# Base_Module.net
KiCad netlist of a schematic drawn in Altium Designer
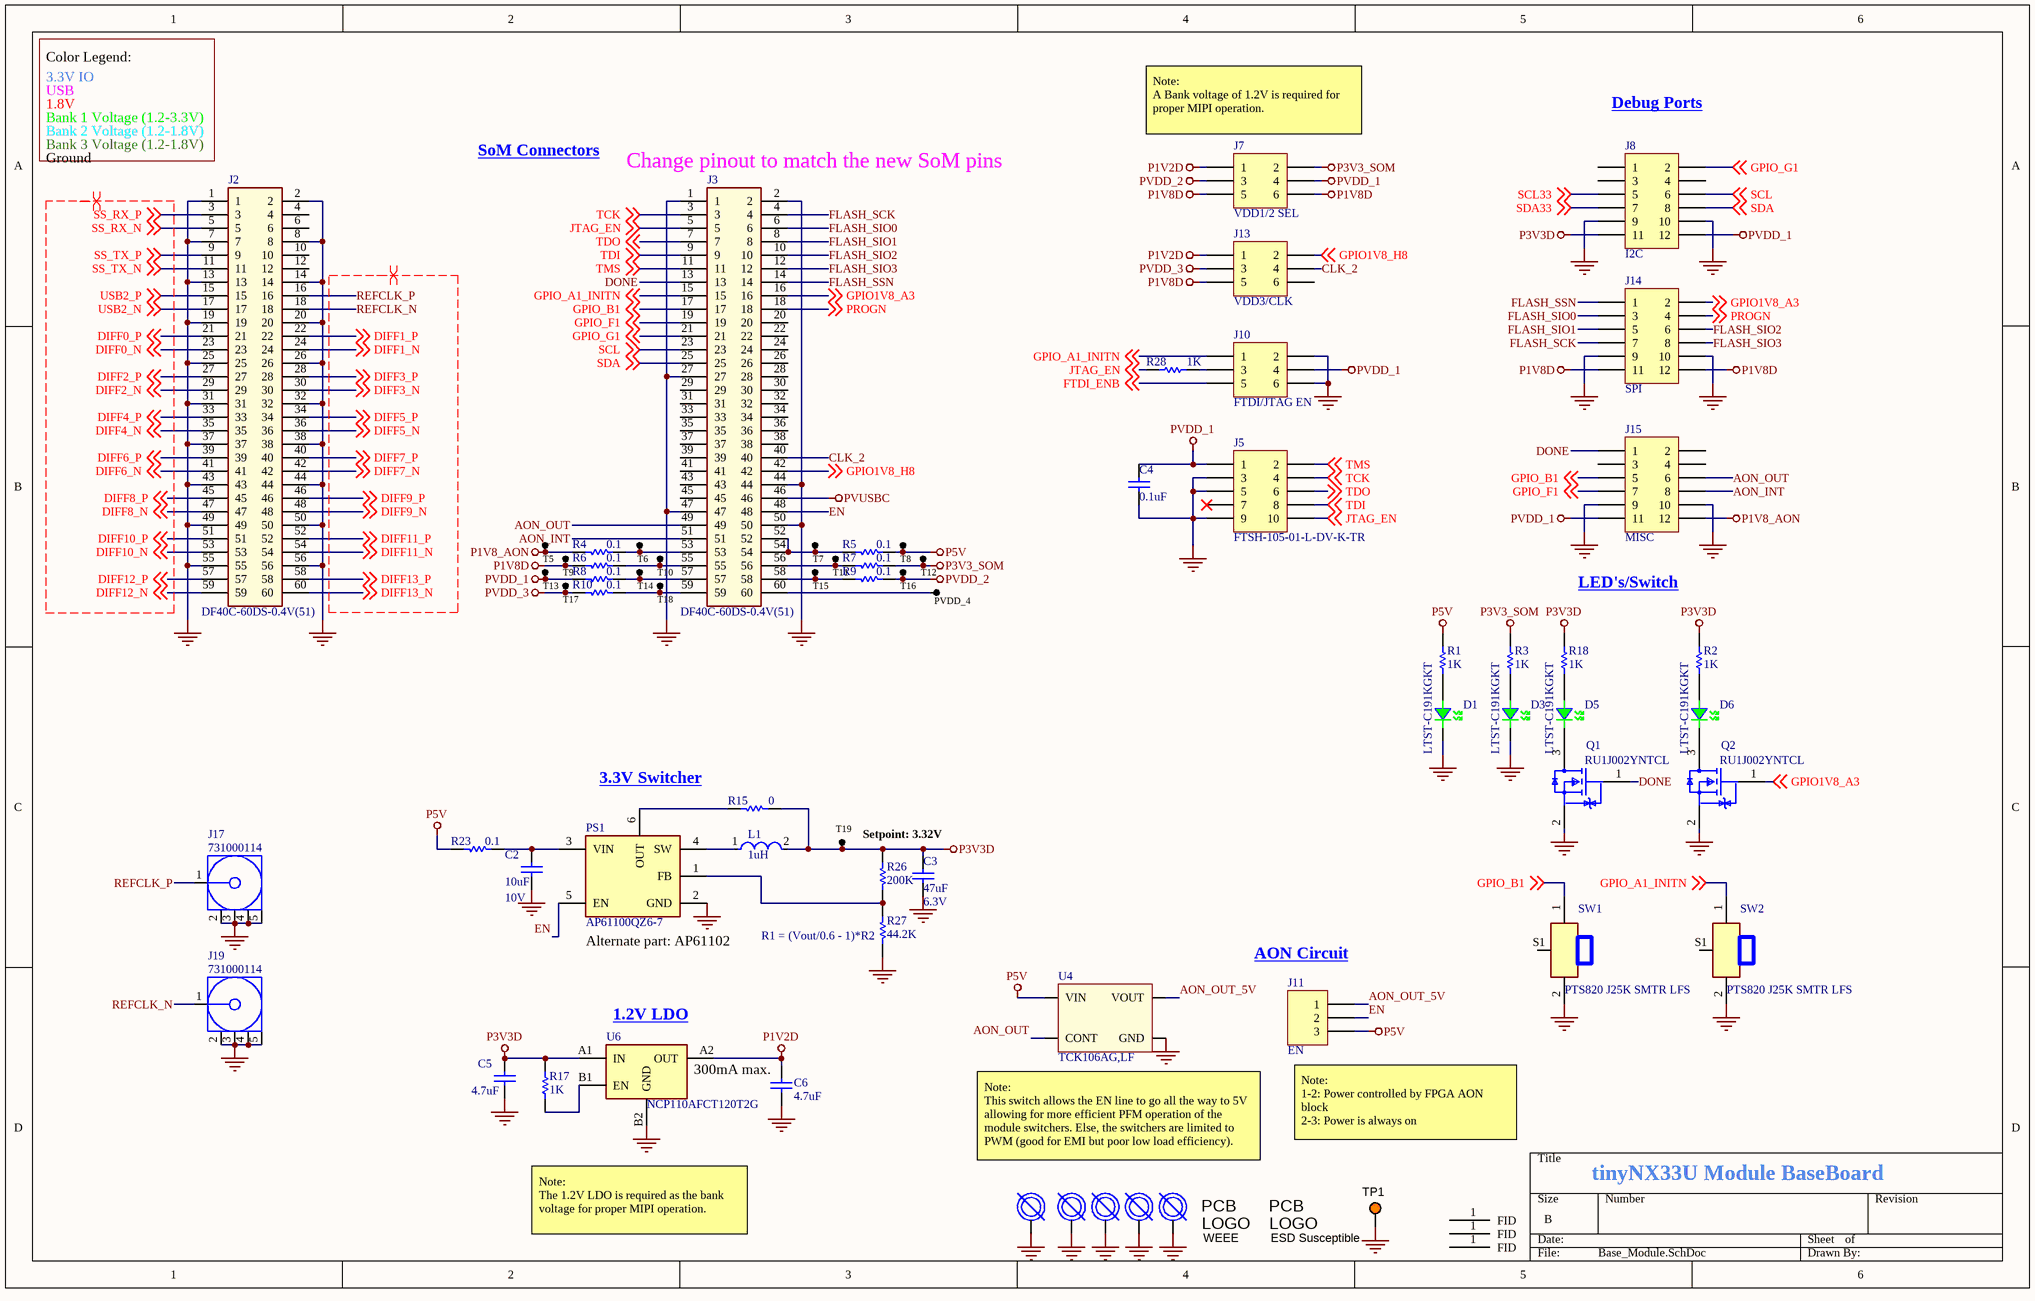
[diagram p0: Base_Module.SchDoc]

(export (version "E")
  (design (tool "Eeschema 10.0.6"))
  (components
    (comp (ref "BH1")
      (value "STANDOFF M2.5")
      (footprint "MH_3MM")
      (description "ROUND STANDOFF M2X0.4 STEEL 1MM")
      (libsource (lib "MIPI_xlator") (part "MOUNT_HOLE"))
    )
    (comp (ref "BH2")
      (value "STANDOFF M2.5")
      (footprint "MH_3MM")
      (description "ROUND STANDOFF M2X0.4 STEEL 1MM")
      (libsource (lib "MIPI_xlator") (part "MOUNT_HOLE"))
    )
    (comp (ref "BH3")
      (value "STANDOFF M2.5")
      (footprint "MH_3MM")
      (description "ROUND STANDOFF M2X0.4 STEEL 1MM")
      (libsource (lib "MIPI_xlator") (part "MOUNT_HOLE"))
    )
    (comp (ref "BH4")
      (value "STANDOFF M2.5")
      (footprint "MH_3MM")
      (description "ROUND STANDOFF M2X0.4 STEEL 1MM")
      (libsource (lib "MIPI_xlator") (part "MOUNT_HOLE"))
    )
    (comp (ref "BH5")
      (value "STANDOFF M2.5")
      (footprint "MH_3MM")
      (description "ROUND STANDOFF M2X0.4 STEEL 1MM")
      (libsource (lib "MIPI_xlator") (part "MOUNT_HOLE"))
    )
    (comp (ref "C2")
      (value "10uF")
      (footprint "CAP_0603")
      (description "CAP CER 10uF 10V X5R 0603")
      (fields
        (field (name "MANUFACTURER PART NUMBER") "GRM188R61A106ME69D")
        (field (name "MANUFACTURER") "Murata Electronics")
        (field (name "VOLTAGE") "10V")
      )
      (libsource (lib "Smart Camera") (part "Cap_1uF_X5R_10%_6V3_0402"))
    )
    (comp (ref "C3")
      (value "47uF")
      (footprint "CAP_0603")
      (description "CAP CER 47UF 6.3V X5R 0603")
      (fields
        (field (name "MANUFACTURER PART NUMBER") "GRM188R60J476ME15D")
        (field (name "MANUFACTURER") "Murata Electronics")
        (field (name "VOLTAGE") "6.3V")
      )
      (libsource (lib "Smart Camera") (part "Cap_1uF_X5R_10%_6V3_0402"))
    )
    (comp (ref "C4")
      (value "0.1uF")
      (footprint "CAPC1005X55USR")
      (description "CAP CER 0.1UF 16V X7R 0402")
      (fields
        (field (name "MANUFACTURER PART NUMBER") "CGA2B1X7R1C104K050BC")
        (field (name "MANUFACTURER") "TDK Corporation")
      )
      (libsource (lib "NX Module baseboard") (part "CAP CER 0.1UF 16V X7R 0402"))
    )
    (comp (ref "C5")
      (value "4.7uF")
      (footprint "CAPC1005X55USR")
      (description "CAP CER 4.7UF 10V X5R 0402")
      (fields
        (field (name "MANUFACTURER PART NUMBER") "C1005X5R1A475M050BC")
        (field (name "MANUFACTURER") "TDK Corporation")
      )
      (libsource (lib "NX Module baseboard") (part "CAP CER 4.7UF 10V X5R 0402"))
    )
    (comp (ref "C6")
      (value "4.7uF")
      (footprint "CAPC1005X55USR")
      (description "CAP CER 4.7UF 10V X5R 0402")
      (fields
        (field (name "MANUFACTURER PART NUMBER") "C1005X5R1A475M050BC")
        (field (name "MANUFACTURER") "TDK Corporation")
      )
      (libsource (lib "NX Module baseboard") (part "CAP CER 4.7UF 10V X5R 0402"))
    )
    (comp (ref "D1")
      (value "LTST-C191KGKT")
      (footprint "LED_0603")
      (description "LED GREEN CLEAR CHIP 0603 SMD")
      (fields
        (field (name "MANUFACTURER") "Lite-On Inc.")
        (field (name "MANUFACTURER PART NUMBER") "LTST-C191GKT")
      )
      (libsource (lib "Tiger_Ti180") (part "0603LED_GRN"))
    )
    (comp (ref "D3")
      (value "LTST-C191KGKT")
      (footprint "LED_0603")
      (description "LED GREEN CLEAR CHIP 0603 SMD")
      (fields
        (field (name "MANUFACTURER") "Lite-On Inc.")
        (field (name "MANUFACTURER PART NUMBER") "LTST-C191GKT")
      )
      (libsource (lib "Tiger_Ti180") (part "0603LED_GRN"))
    )
    (comp (ref "D5")
      (value "LTST-C191KGKT")
      (footprint "LED_0603")
      (description "LED GREEN CLEAR CHIP 0603 SMD")
      (fields
        (field (name "MANUFACTURER") "Lite-On Inc.")
        (field (name "MANUFACTURER PART NUMBER") "LTST-C191GKT")
      )
      (libsource (lib "Tiger_Ti180") (part "0603LED_GRN"))
    )
    (comp (ref "D6")
      (value "LTST-C191KGKT")
      (footprint "LED_0603")
      (description "LED GREEN CLEAR CHIP 0603 SMD")
      (fields
        (field (name "MANUFACTURER") "Lite-On Inc.")
        (field (name "MANUFACTURER PART NUMBER") "LTST-C191GKT")
      )
      (libsource (lib "Tiger_Ti180") (part "0603LED_GRN"))
    )
    (comp (ref "FID1") (value "~") (footprint "FID_040") (libsource (lib "MIPI_xlator") (part "FID")))
    (comp (ref "FID2") (value "~") (footprint "FID_040") (libsource (lib "MIPI_xlator") (part "FID")))
    (comp (ref "FID3") (value "~") (footprint "FID_040") (libsource (lib "MIPI_xlator") (part "FID")))
    (comp (ref "J2")
      (value "DF40C-60DS-0.4V(51)")
      (footprint "DF40C60DS04V51")
      (description "CONN RCPT 60POS SMD GOLD")
      (fields (field (name "MANUFACTURER") "Hirose"))
      (libsource (lib "NX Module baseboard") (part "DF40C-60DS-0.4V(51)"))
    )
    (comp (ref "J3")
      (value "DF40C-60DS-0.4V(51)")
      (footprint "DF40C60DS04V51")
      (description "CONN RCPT 60POS SMD GOLD")
      (fields (field (name "MANUFACTURER") "Hirose"))
      (libsource (lib "NX Module baseboard") (part "DF40C-60DS-0.4V(51)"))
    )
    (comp (ref "J5")
      (value "FTSH-105-01-L-DV-K-TR")
      (footprint "FTSH-105-01-XXX-DV-K")
      (description "CONN HEADER SMD 10POS 1.27MM")
      (fields (field (name "MANUFACTURER") "Samtec Inc."))
      (libsource (lib "tinyAI") (part "HDR2X5_1.27mm"))
    )
    (comp (ref "J7")
      (value "Header 3X2_SMD")
      (footprint "HDR3X2_MALE_2.54MM_SAMTEC-A-TSM-103")
      (description "Conn Unshrouded Header HDR 6 POS 2.54mm Solder ST Top Entry SMD Tube")
      (fields
        (field (name "MANUFACTURER") "Samtec")
        (field (name "MANUFACTURER PART NUMBER") "TSM-103-01-L-DV")
        (field (name "CONTENT") "VDD1/2 SEL")
      )
      (libsource (lib "NX Module baseboard") (part "Header 3X2_SMD"))
    )
    (comp (ref "J8")
      (value "Header 6X2_SMD")
      (footprint "HDR6X2_MALE_2.54MM_SAMTEC-A-TSM-106")
      (description "Conn Unshrouded Header HDR 12 POS 2.54mm Solder ST Top Entry SMD Tube")
      (fields
        (field (name "MANUFACTURER") "Samtec")
        (field (name "MANUFACTURER PART NUMBER") "TSM-106-01-L-DV")
        (field (name "CONTENT") "I2C")
      )
      (libsource (lib "NX Module baseboard") (part "Header 6X2_SMD"))
    )
    (comp (ref "J10")
      (value "Header 3X2_SMD")
      (footprint "HDR3X2_MALE_2.54MM_SAMTEC-A-TSM-103")
      (description "Conn Unshrouded Header HDR 6 POS 2.54mm Solder ST Top Entry SMD Tube")
      (fields
        (field (name "MANUFACTURER") "Samtec")
        (field (name "MANUFACTURER PART NUMBER") "TSM-103-01-L-DV")
        (field (name "CONTENT") "FTDI/JTAG EN")
      )
      (libsource (lib "NX Module baseboard") (part "Header 3X2_SMD"))
    )
    (comp (ref "J11")
      (value "Header 3X1_2.54MM")
      (footprint "HDR3X1_MALE_2.54MM")
      (description "CONN HEADER .100 SNGL STR 3POS")
      (fields
        (field (name "MANUFACTURER") "Sullins")
        (field (name "MANUFACTURER PART NUMBER") "PRPC003SAAN-RC")
        (field (name "CONTENT") "EN")
      )
      (libsource (lib "NX Module baseboard") (part "Header 3X1_2.54MM"))
    )
    (comp (ref "J13")
      (value "Header 3X2_SMD")
      (footprint "HDR3X2_MALE_2.54MM_SAMTEC-A-TSM-103")
      (description "Conn Unshrouded Header HDR 6 POS 2.54mm Solder ST Top Entry SMD Tube")
      (fields
        (field (name "MANUFACTURER") "Samtec")
        (field (name "MANUFACTURER PART NUMBER") "TSM-103-01-L-DV")
        (field (name "CONTENT") "VDD3/CLK")
      )
      (libsource (lib "NX Module baseboard") (part "Header 3X2_SMD"))
    )
    (comp (ref "J14")
      (value "Header 6X2_SMD")
      (footprint "HDR6X2_MALE_2.54MM_SAMTEC-A-TSM-106")
      (description "Conn Unshrouded Header HDR 12 POS 2.54mm Solder ST Top Entry SMD Tube")
      (fields
        (field (name "MANUFACTURER") "Samtec")
        (field (name "MANUFACTURER PART NUMBER") "TSM-106-01-L-DV")
        (field (name "CONTENT") "SPI")
      )
      (libsource (lib "NX Module baseboard") (part "Header 6X2_SMD"))
    )
    (comp (ref "J15")
      (value "Header 6X2_SMD")
      (footprint "HDR6X2_MALE_2.54MM_SAMTEC-A-TSM-106")
      (description "Conn Unshrouded Header HDR 12 POS 2.54mm Solder ST Top Entry SMD Tube")
      (fields
        (field (name "MANUFACTURER") "Samtec")
        (field (name "MANUFACTURER PART NUMBER") "TSM-106-01-L-DV")
        (field (name "CONTENT") "MISC")
      )
      (libsource (lib "NX Module baseboard") (part "Header 6X2_SMD"))
    )
    (comp (ref "J17")
      (value "731000114")
      (footprint "0731000114")
      (description "SMA Right-Angle PCB Jack Receptacle, Brass Body, Gold Plated, 50 Ohm, 5-Pin THD, RoHS, Tray")
      (fields (field (name "MANUFACTURER") "Molex") (field (name "MANUFACTURER PART NUMBER") "73100-0114"))
      (libsource (lib "NX Module baseboard") (part "CN-S-4F-RF5"))
    )
    (comp (ref "J19")
      (value "731000114")
      (footprint "0731000114")
      (description "SMA Right-Angle PCB Jack Receptacle, Brass Body, Gold Plated, 50 Ohm, 5-Pin THD, RoHS, Tray")
      (fields (field (name "MANUFACTURER") "Molex") (field (name "MANUFACTURER PART NUMBER") "73100-0114"))
      (libsource (lib "NX Module baseboard") (part "CN-S-4F-RF5"))
    )
    (comp (ref "L1")
      (value "1uH")
      (footprint "INDC2016X100N")
      (description "FIXED IND 1UH 2.7A 57 MOHM SMD")
      (fields
        (field (name "MANUFACTURER") "Murata Electronics")
        (field (name "MANUFACTURER PART NUMBER") "DFE201610E-1R0M=P2")
      )
      (libsource (lib "Smart Camera") (part "725321dda6339637d4d059423bc1c3c"))
    )
    (comp (ref "Logo1")
      (value "WEEE")
      (footprint "WEEE_Minimum")
      (description "WEEE logo")
      (libsource (lib "MIPI_xlator") (part "Logo WEEE"))
    )
    (comp (ref "Logo2")
      (value "ESD Susceptible")
      (footprint "ESD_Overlay_Medium")
      (description "ESD Susceptible Symbol")
      (fields (field (name "PUBLISHER") "Texas Instruments") (field (name "SYMBOLCREATOR") "a0412235"))
      (libsource (lib "MIPI_xlator") (part "Logo ESD"))
    )
    (comp (ref "PS1")
      (value "AP61100QZ6-7")
      (footprint "SOTFL50P160X60-6N")
      (description "DC-DC CONV LV BUCK SOT563")
      (fields (field (name "MANUFACTURER") "Diodes Incorporated"))
      (libsource (lib "Smart Camera") (part "AP61100Z6-7"))
    )
    (comp (ref "PVDD_4")
      (value "TP_S")
      (footprint "TP_TH")
      (description "test point")
      (libsource (lib "AiC") (part "TP_S"))
    )
    (comp (ref "Q1")
      (value "RU1J002YNTCL")
      (footprint "SOT-323FL")
      (description "MOSFET N-CH 50V 0.2A UMT3F")
      (fields
        (field (name "MANUFACTURER") "Rohm")
        (field (name "OCTOPART") "https://octopart.com/ru1j002yntcl-rohm-47197697")
      )
      (libsource (lib "AiC") (part "1926738d861a973c8d722c53ec8fd09"))
    )
    (comp (ref "Q2")
      (value "RU1J002YNTCL")
      (footprint "SOT-323FL")
      (description "MOSFET N-CH 50V 0.2A UMT3F")
      (fields
        (field (name "MANUFACTURER") "Rohm")
        (field (name "OCTOPART") "https://octopart.com/ru1j002yntcl-rohm-47197697")
      )
      (libsource (lib "AiC") (part "1926738d861a973c8d722c53ec8fd09"))
    )
    (comp (ref "R1")
      (value "1K")
      (footprint "RESC1005X40USR")
      (description "RES SMD 1K OHM 1% 1/16W 0402")
      (fields
        (field (name "MANUFACTURER") "YAGEO")
        (field (name "MANUFACTURER PART NUMBER") "RC0402FR-071KL")
      )
      (libsource (lib "Tiger_Ti180") (part "RES 1K OHM 1% 1/16W 0402"))
    )
    (comp (ref "R2")
      (value "1K")
      (footprint "RESC1005X40USR")
      (description "RES SMD 1K OHM 1% 1/16W 0402")
      (fields
        (field (name "MANUFACTURER") "YAGEO")
        (field (name "MANUFACTURER PART NUMBER") "RC0402FR-071KL")
      )
      (libsource (lib "Tiger_Ti180") (part "RES 1K OHM 1% 1/16W 0402"))
    )
    (comp (ref "R3")
      (value "1K")
      (footprint "RESC1005X40USR")
      (description "RES SMD 1K OHM 1% 1/16W 0402")
      (fields
        (field (name "MANUFACTURER") "YAGEO")
        (field (name "MANUFACTURER PART NUMBER") "RC0402FR-071KL")
      )
      (libsource (lib "Tiger_Ti180") (part "RES 1K OHM 1% 1/16W 0402"))
    )
    (comp (ref "R4")
      (value "0.1")
      (footprint "RESC1005X40USR")
      (description "RES 0.1 OHM 1% 1/8W 0402")
      (fields
        (field (name "MANUFACTURER PART NUMBER") "CSR0402FKR100")
        (field (name "MANUFACTURER") "Stackpole Electronics Inc")
      )
      (libsource (lib "tinyAI") (part "RES 0.5 OHM 1% 1/8W 0402"))
    )
    (comp (ref "R5")
      (value "0.1")
      (footprint "RESC1005X40USR")
      (description "RES 0.1 OHM 1% 1/8W 0402")
      (fields
        (field (name "MANUFACTURER PART NUMBER") "CSR0402FKR100")
        (field (name "MANUFACTURER") "Stackpole Electronics Inc")
      )
      (libsource (lib "tinyAI") (part "RES 0.5 OHM 1% 1/8W 0402"))
    )
    (comp (ref "R6")
      (value "0.1")
      (footprint "RESC1005X40USR")
      (description "RES 0.1 OHM 1% 1/8W 0402")
      (fields
        (field (name "MANUFACTURER PART NUMBER") "CSR0402FKR100")
        (field (name "MANUFACTURER") "Stackpole Electronics Inc")
      )
      (libsource (lib "tinyAI") (part "RES 0.5 OHM 1% 1/8W 0402"))
    )
    (comp (ref "R7")
      (value "0.1")
      (footprint "RESC1005X40USR")
      (description "RES 0.1 OHM 1% 1/8W 0402")
      (fields
        (field (name "MANUFACTURER PART NUMBER") "CSR0402FKR100")
        (field (name "MANUFACTURER") "Stackpole Electronics Inc")
      )
      (libsource (lib "tinyAI") (part "RES 0.5 OHM 1% 1/8W 0402"))
    )
    (comp (ref "R8")
      (value "0.1")
      (footprint "RESC1005X40USR")
      (description "RES 0.1 OHM 1% 1/8W 0402")
      (fields
        (field (name "MANUFACTURER PART NUMBER") "CSR0402FKR100")
        (field (name "MANUFACTURER") "Stackpole Electronics Inc")
      )
      (libsource (lib "tinyAI") (part "RES 0.5 OHM 1% 1/8W 0402"))
    )
    (comp (ref "R9")
      (value "0.1")
      (footprint "RESC1005X40USR")
      (description "RES 0.1 OHM 1% 1/8W 0402")
      (fields
        (field (name "MANUFACTURER PART NUMBER") "CSR0402FKR100")
        (field (name "MANUFACTURER") "Stackpole Electronics Inc")
      )
      (libsource (lib "tinyAI") (part "RES 0.5 OHM 1% 1/8W 0402"))
    )
    (comp (ref "R10")
      (value "0.1")
      (footprint "RESC1005X40USR")
      (description "RES 0.1 OHM 1% 1/8W 0402")
      (fields
        (field (name "MANUFACTURER PART NUMBER") "CSR0402FKR100")
        (field (name "MANUFACTURER") "Stackpole Electronics Inc")
      )
      (libsource (lib "tinyAI") (part "RES 0.5 OHM 1% 1/8W 0402"))
    )
    (comp (ref "R15")
      (value "0")
      (footprint "RESC1005X40USR")
      (description "RES 0 OHM JUMPER 1/16W 0402")
      (fields
        (field (name "MANUFACTURER") "Yageo")
        (field (name "MANUFACTURER PART NUMBER") "RC0402JR-070RL")
      )
      (libsource (lib "Smart Camera v2") (part "RES 0 OHM JUMPER 1/20W 0201"))
    )
    (comp (ref "R17")
      (value "1K")
      (footprint "RESC1005X40USR")
      (description "RES SMD 1K OHM 1% 1/16W 0402")
      (fields
        (field (name "MANUFACTURER") "YAGEO")
        (field (name "MANUFACTURER PART NUMBER") "RC0402FR-071KL")
      )
      (libsource (lib "Tiger_Ti180") (part "RES 1K OHM 1% 1/16W 0402"))
    )
    (comp (ref "R18")
      (value "1K")
      (footprint "RESC1005X40USR")
      (description "RES SMD 1K OHM 1% 1/16W 0402")
      (fields
        (field (name "MANUFACTURER") "YAGEO")
        (field (name "MANUFACTURER PART NUMBER") "RC0402FR-071KL")
      )
      (libsource (lib "Tiger_Ti180") (part "RES 1K OHM 1% 1/16W 0402"))
    )
    (comp (ref "R23")
      (value "0.1")
      (footprint "RESC1005X40USR")
      (description "RES 0.1 OHM 1% 1/8W 0402")
      (fields
        (field (name "MANUFACTURER PART NUMBER") "CSR0402FKR100")
        (field (name "MANUFACTURER") "Stackpole Electronics Inc")
      )
      (libsource (lib "tinyAI") (part "RES 0.5 OHM 1% 1/8W 0402"))
    )
    (comp (ref "R26")
      (value "200K")
      (footprint "RESC1005X40USR")
      (description "RES SMD 200K OHM 1% 1/16W 0402")
      (fields
        (field (name "MANUFACTURER") "Stackpole Electronics Inc")
        (field (name "MANUFACTURER PART NUMBER") "RMCF0402FT200K")
      )
      (libsource (lib "MCD_Temp_LBE") (part "Res_10K_1%_0402"))
    )
    (comp (ref "R27")
      (value "44.2K")
      (footprint "RESC1005X40USR")
      (description "RES SMD 44.2K OHM 1% 1/16W 0402")
      (fields
        (field (name "MANUFACTURER") "Yageo")
        (field (name "MANUFACTURER PART NUMBER") "RC0402FR-0744K2L")
      )
      (libsource (lib "MCD_Temp_LBE") (part "Res_10K_1%_0402"))
    )
    (comp (ref "R28")
      (value "1K")
      (footprint "RESC1005X40USR")
      (description "RES SMD 1K OHM 1% 1/16W 0402")
      (fields
        (field (name "MANUFACTURER") "YAGEO")
        (field (name "MANUFACTURER PART NUMBER") "RC0402FR-071KL")
      )
      (libsource (lib "Tiger_Ti180") (part "RES 1K OHM 1% 1/16W 0402"))
    )
    (comp (ref "SW1")
      (value "PTS820 J25K SMTR LFS")
      (footprint "PTS820J25MSMTRLFS")
      (description "SWITCH TACTILE SPST-NO 0.05A 12V")
      (fields (field (name "MANUFACTURER") "C&K"))
      (libsource (lib "Tiger_Ti180") (part "SPST_NO"))
    )
    (comp (ref "SW2")
      (value "PTS820 J25K SMTR LFS")
      (footprint "PTS820J25MSMTRLFS")
      (description "SWITCH TACTILE SPST-NO 0.05A 12V")
      (fields (field (name "MANUFACTURER") "C&K"))
      (libsource (lib "Tiger_Ti180") (part "SPST_NO"))
    )
    (comp (ref "T5")
      (value "TP_S")
      (footprint "TP_TH")
      (description "test point")
      (libsource (lib "AiC") (part "TP_S"))
    )
    (comp (ref "T6")
      (value "TP_S")
      (footprint "TP_TH")
      (description "test point")
      (libsource (lib "AiC") (part "TP_S"))
    )
    (comp (ref "T7")
      (value "TP_S")
      (footprint "TP_TH")
      (description "test point")
      (libsource (lib "AiC") (part "TP_S"))
    )
    (comp (ref "T8")
      (value "TP_S")
      (footprint "TP_TH")
      (description "test point")
      (libsource (lib "AiC") (part "TP_S"))
    )
    (comp (ref "T9")
      (value "TP_S")
      (footprint "TP_TH")
      (description "test point")
      (libsource (lib "AiC") (part "TP_S"))
    )
    (comp (ref "T10")
      (value "TP_S")
      (footprint "TP_TH")
      (description "test point")
      (libsource (lib "AiC") (part "TP_S"))
    )
    (comp (ref "T11")
      (value "TP_S")
      (footprint "TP_TH")
      (description "test point")
      (libsource (lib "AiC") (part "TP_S"))
    )
    (comp (ref "T12")
      (value "TP_S")
      (footprint "TP_TH")
      (description "test point")
      (libsource (lib "AiC") (part "TP_S"))
    )
    (comp (ref "T13")
      (value "TP_S")
      (footprint "TP_TH")
      (description "test point")
      (libsource (lib "AiC") (part "TP_S"))
    )
    (comp (ref "T14")
      (value "TP_S")
      (footprint "TP_TH")
      (description "test point")
      (libsource (lib "AiC") (part "TP_S"))
    )
    (comp (ref "T15")
      (value "TP_S")
      (footprint "TP_TH")
      (description "test point")
      (libsource (lib "AiC") (part "TP_S"))
    )
    (comp (ref "T16")
      (value "TP_S")
      (footprint "TP_TH")
      (description "test point")
      (libsource (lib "AiC") (part "TP_S"))
    )
    (comp (ref "T17")
      (value "TP_S")
      (footprint "TP_TH")
      (description "test point")
      (libsource (lib "AiC") (part "TP_S"))
    )
    (comp (ref "T18")
      (value "TP_S")
      (footprint "TP_TH")
      (description "test point")
      (libsource (lib "AiC") (part "TP_S"))
    )
    (comp (ref "T19")
      (value "3V3")
      (footprint "TP 1mm")
      (description "test point")
      (libsource (lib "Smart Camera") (part "TP_S"))
    )
    (comp (ref "TP1")
      (value "5019")
      (footprint "TP380X203")
      (description "PC TEST POINT MINIATURE")
      (fields (field (name "MANUFACTURER") "Keystone Electronics"))
      (libsource (lib "MIPI_xlator") (part "5019"))
    )
    (comp (ref "U4")
      (value "TCK106AG,LF")
      (footprint "WCSP4D")
      (description "IC PWR SWITCH P-CHAN 1:1 4WCSPD")
      (fields
        (field (name "MANUFACTURER") "Toshiba")
        (field (name "COPYRIGHT") "Copyright (C) 2018 Accelerated Designs. All rights reserved")
      )
      (libsource (lib "tinyAI") (part "TCK106AG"))
    )
    (comp (ref "U6")
      (value "NCP110AFCT120T2G")
      (footprint "WLCSP4_P6XP6_ONS")
      (description "LDO Regulator, 200 mA, Low Vin, Ultra-High PSRR 1.2V, Active Discharge")
      (fields (field (name "MANUFACTURER") "ON Semiconductor"))
      (libsource (lib "Tiger_Ti180") (part "NCP110AFCT120T2G"))
    )
  )
  (nets
    (net (code "1") (name "/AON_INT") (class "Default")
      (node (ref "J15") (pin "8") (pinfunction "8_8") (pintype "passive"))
      (node (ref "J3") (pin "51") (pinfunction "51_51") (pintype "passive"))
    )
    (net (code "2") (name "/AON_OUT") (class "Default")
      (node (ref "J15") (pin "6") (pinfunction "6_6") (pintype "passive"))
      (node (ref "J3") (pin "49") (pinfunction "49_49") (pintype "passive"))
      (node (ref "U4") (pin "B2") (pinfunction "CONT_B2") (pintype "passive"))
    )
    (net (code "3") (name "/AON_OUT_5V") (class "Default")
      (node (ref "J11") (pin "1") (pinfunction "1_1") (pintype "passive"))
      (node (ref "U4") (pin "A1") (pinfunction "VOUT_A1") (pintype "passive"))
    )
    (net (code "4") (name "/CLK_2") (class "Default")
      (node (ref "J13") (pin "4") (pinfunction "4_4") (pintype "passive"))
      (node (ref "J3") (pin "40") (pinfunction "40_40") (pintype "passive"))
    )
    (net (code "5") (name "/DONE") (class "Default")
      (node (ref "J15") (pin "1") (pinfunction "1_1") (pintype "passive"))
      (node (ref "J3") (pin "13") (pinfunction "13_13") (pintype "passive"))
      (node (ref "Q1") (pin "1") (pinfunction "G_1") (pintype "passive"))
    )
    (net (code "6") (name "/EN") (class "Default")
      (node (ref "J11") (pin "2") (pinfunction "2_2") (pintype "passive"))
      (node (ref "J3") (pin "48") (pinfunction "48_48") (pintype "passive"))
      (node (ref "PS1") (pin "5") (pinfunction "EN_5") (pintype "passive"))
    )
    (net (code "7") (name "/FLASH_SCK") (class "Default")
      (node (ref "J14") (pin "7") (pinfunction "7_7") (pintype "passive"))
      (node (ref "J3") (pin "4") (pinfunction "4_4") (pintype "passive"))
    )
    (net (code "8") (name "/FLASH_SIO0") (class "Default")
      (node (ref "J14") (pin "3") (pinfunction "3_3") (pintype "passive"))
      (node (ref "J3") (pin "6") (pinfunction "6_6") (pintype "passive"))
    )
    (net (code "9") (name "/FLASH_SIO1") (class "Default")
      (node (ref "J14") (pin "5") (pinfunction "5_5") (pintype "passive"))
      (node (ref "J3") (pin "8") (pinfunction "8_8") (pintype "passive"))
    )
    (net (code "10") (name "/FLASH_SIO2") (class "Default")
      (node (ref "J14") (pin "6") (pinfunction "6_6") (pintype "passive"))
      (node (ref "J3") (pin "10") (pinfunction "10_10") (pintype "passive"))
    )
    (net (code "11") (name "/FLASH_SIO3") (class "Default")
      (node (ref "J14") (pin "8") (pinfunction "8_8") (pintype "passive"))
      (node (ref "J3") (pin "12") (pinfunction "12_12") (pintype "passive"))
    )
    (net (code "12") (name "/FLASH_SSN") (class "Default")
      (node (ref "J14") (pin "1") (pinfunction "1_1") (pintype "passive"))
      (node (ref "J3") (pin "14") (pinfunction "14_14") (pintype "passive"))
    )
    (net (code "13") (name "/REFCLK_N") (class "Default")
      (node (ref "J19") (pin "1") (pinfunction "1_1") (pintype "passive"))
      (node (ref "J2") (pin "18") (pinfunction "18_18") (pintype "passive"))
    )
    (net (code "14") (name "/REFCLK_P") (class "Default")
      (node (ref "J17") (pin "1") (pinfunction "1_1") (pintype "passive"))
      (node (ref "J2") (pin "16") (pinfunction "16_16") (pintype "passive"))
    )
    (net (code "15") (name "DIFF0_N") (class "Default")
      (node (ref "J2") (pin "23") (pinfunction "23_23") (pintype "passive"))
    )
    (net (code "16") (name "DIFF0_P") (class "Default")
      (node (ref "J2") (pin "21") (pinfunction "21_21") (pintype "passive"))
    )
    (net (code "17") (name "DIFF1_N") (class "Default")
      (node (ref "J2") (pin "24") (pinfunction "24_24") (pintype "passive"))
    )
    (net (code "18") (name "DIFF1_P") (class "Default")
      (node (ref "J2") (pin "22") (pinfunction "22_22") (pintype "passive"))
    )
    (net (code "19") (name "DIFF2_N") (class "Default")
      (node (ref "J2") (pin "29") (pinfunction "29_29") (pintype "passive"))
    )
    (net (code "20") (name "DIFF2_P") (class "Default")
      (node (ref "J2") (pin "27") (pinfunction "27_27") (pintype "passive"))
    )
    (net (code "21") (name "DIFF3_N") (class "Default")
      (node (ref "J2") (pin "30") (pinfunction "30_30") (pintype "passive"))
    )
    (net (code "22") (name "DIFF3_P") (class "Default")
      (node (ref "J2") (pin "28") (pinfunction "28_28") (pintype "passive"))
    )
    (net (code "23") (name "DIFF4_N") (class "Default")
      (node (ref "J2") (pin "35") (pinfunction "35_35") (pintype "passive"))
    )
    (net (code "24") (name "DIFF4_P") (class "Default")
      (node (ref "J2") (pin "33") (pinfunction "33_33") (pintype "passive"))
    )
    (net (code "25") (name "DIFF5_N") (class "Default")
      (node (ref "J2") (pin "36") (pinfunction "36_36") (pintype "passive"))
    )
    (net (code "26") (name "DIFF5_P") (class "Default")
      (node (ref "J2") (pin "34") (pinfunction "34_34") (pintype "passive"))
    )
    (net (code "27") (name "DIFF6_N") (class "Default")
      (node (ref "J2") (pin "41") (pinfunction "41_41") (pintype "passive"))
    )
    (net (code "28") (name "DIFF6_P") (class "Default")
      (node (ref "J2") (pin "39") (pinfunction "39_39") (pintype "passive"))
    )
    (net (code "29") (name "DIFF7_N") (class "Default")
      (node (ref "J2") (pin "42") (pinfunction "42_42") (pintype "passive"))
    )
    (net (code "30") (name "DIFF7_P") (class "Default")
      (node (ref "J2") (pin "40") (pinfunction "40_40") (pintype "passive"))
    )
    (net (code "31") (name "DIFF8_N") (class "Default")
      (node (ref "J2") (pin "47") (pinfunction "47_47") (pintype "passive"))
    )
    (net (code "32") (name "DIFF8_P") (class "Default")
      (node (ref "J2") (pin "45") (pinfunction "45_45") (pintype "passive"))
    )
    (net (code "33") (name "DIFF9_N") (class "Default")
      (node (ref "J2") (pin "48") (pinfunction "48_48") (pintype "passive"))
    )
    (net (code "34") (name "DIFF9_P") (class "Default")
      (node (ref "J2") (pin "46") (pinfunction "46_46") (pintype "passive"))
    )
    (net (code "35") (name "DIFF10_N") (class "Default")
      (node (ref "J2") (pin "53") (pinfunction "53_53") (pintype "passive"))
    )
    (net (code "36") (name "DIFF10_P") (class "Default")
      (node (ref "J2") (pin "51") (pinfunction "51_51") (pintype "passive"))
    )
    (net (code "37") (name "DIFF11_N") (class "Default")
      (node (ref "J2") (pin "54") (pinfunction "54_54") (pintype "passive"))
    )
    (net (code "38") (name "DIFF11_P") (class "Default")
      (node (ref "J2") (pin "52") (pinfunction "52_52") (pintype "passive"))
    )
    (net (code "39") (name "DIFF12_N") (class "Default")
      (node (ref "J2") (pin "59") (pinfunction "59_59") (pintype "passive"))
    )
    (net (code "40") (name "DIFF12_P") (class "Default")
      (node (ref "J2") (pin "57") (pinfunction "57_57") (pintype "passive"))
    )
    (net (code "41") (name "DIFF13_N") (class "Default")
      (node (ref "J2") (pin "60") (pinfunction "60_60") (pintype "passive"))
    )
    (net (code "42") (name "DIFF13_P") (class "Default")
      (node (ref "J2") (pin "58") (pinfunction "58_58") (pintype "passive"))
    )
    (net (code "43") (name "FTDI_ENB") (class "Default")
      (node (ref "J10") (pin "5") (pinfunction "5_5") (pintype "passive"))
    )
    (net (code "44") (name "GND") (class "Default")
      (node (ref "BH1") (pin "1") (pinfunction "1_1") (pintype "passive"))
      (node (ref "BH2") (pin "1") (pinfunction "1_1") (pintype "passive"))
      (node (ref "BH3") (pin "1") (pinfunction "1_1") (pintype "passive"))
      (node (ref "BH4") (pin "1") (pinfunction "1_1") (pintype "passive"))
      (node (ref "BH5") (pin "1") (pinfunction "1_1") (pintype "passive"))
      (node (ref "C2") (pin "1") (pinfunction "1_1") (pintype "passive"))
      (node (ref "C3") (pin "1") (pinfunction "1_1") (pintype "passive"))
      (node (ref "C4") (pin "1") (pinfunction "1_1") (pintype "passive"))
      (node (ref "C5") (pin "1") (pinfunction "1_1") (pintype "passive"))
      (node (ref "C6") (pin "1") (pinfunction "1_1") (pintype "passive"))
      (node (ref "D1") (pin "2") (pinfunction "K_2") (pintype "passive"))
      (node (ref "D3") (pin "2") (pinfunction "K_2") (pintype "passive"))
      (node (ref "J10") (pin "2") (pinfunction "2_2") (pintype "passive"))
      (node (ref "J10") (pin "6") (pinfunction "6_6") (pintype "passive"))
      (node (ref "J14") (pin "10") (pinfunction "10_10") (pintype "passive"))
      (node (ref "J14") (pin "9") (pinfunction "9_9") (pintype "passive"))
      (node (ref "J15") (pin "10") (pinfunction "10_10") (pintype "passive"))
      (node (ref "J15") (pin "9") (pinfunction "9_9") (pintype "passive"))
      (node (ref "J17") (pin "2") (pinfunction "2_2") (pintype "passive"))
      (node (ref "J17") (pin "3") (pinfunction "3_3") (pintype "passive"))
      (node (ref "J17") (pin "4") (pinfunction "4_4") (pintype "passive"))
      (node (ref "J17") (pin "5") (pinfunction "5_5") (pintype "passive"))
      (node (ref "J19") (pin "2") (pinfunction "2_2") (pintype "passive"))
      (node (ref "J19") (pin "3") (pinfunction "3_3") (pintype "passive"))
      (node (ref "J19") (pin "4") (pinfunction "4_4") (pintype "passive"))
      (node (ref "J19") (pin "5") (pinfunction "5_5") (pintype "passive"))
      (node (ref "J2") (pin "1") (pinfunction "1_1") (pintype "passive"))
      (node (ref "J2") (pin "13") (pinfunction "13_13") (pintype "passive"))
      (node (ref "J2") (pin "14") (pinfunction "14_14") (pintype "passive"))
      (node (ref "J2") (pin "19") (pinfunction "19_19") (pintype "passive"))
      (node (ref "J2") (pin "2") (pinfunction "2_2") (pintype "passive"))
      (node (ref "J2") (pin "20") (pinfunction "20_20") (pintype "passive"))
      (node (ref "J2") (pin "25") (pinfunction "25_25") (pintype "passive"))
      (node (ref "J2") (pin "26") (pinfunction "26_26") (pintype "passive"))
      (node (ref "J2") (pin "31") (pinfunction "31_31") (pintype "passive"))
      (node (ref "J2") (pin "32") (pinfunction "32_32") (pintype "passive"))
      (node (ref "J2") (pin "37") (pinfunction "37_37") (pintype "passive"))
      (node (ref "J2") (pin "38") (pinfunction "38_38") (pintype "passive"))
      (node (ref "J2") (pin "43") (pinfunction "43_43") (pintype "passive"))
      (node (ref "J2") (pin "44") (pinfunction "44_44") (pintype "passive"))
      (node (ref "J2") (pin "49") (pinfunction "49_49") (pintype "passive"))
      (node (ref "J2") (pin "50") (pinfunction "50_50") (pintype "passive"))
      (node (ref "J2") (pin "55") (pinfunction "55_55") (pintype "passive"))
      (node (ref "J2") (pin "56") (pinfunction "56_56") (pintype "passive"))
      (node (ref "J2") (pin "7") (pinfunction "7_7") (pintype "passive"))
      (node (ref "J2") (pin "8") (pinfunction "8_8") (pintype "passive"))
      (node (ref "J3") (pin "1") (pinfunction "1_1") (pintype "passive"))
      (node (ref "J3") (pin "2") (pinfunction "2_2") (pintype "passive"))
      (node (ref "J3") (pin "27") (pinfunction "27_27") (pintype "passive"))
      (node (ref "J3") (pin "44") (pinfunction "44_44") (pintype "passive"))
      (node (ref "J3") (pin "47") (pinfunction "47_47") (pintype "passive"))
      (node (ref "J3") (pin "50") (pinfunction "50_50") (pintype "passive"))
      (node (ref "J5") (pin "3") (pinfunction "3_3") (pintype "passive"))
      (node (ref "J5") (pin "5") (pinfunction "5_5") (pintype "passive"))
      (node (ref "J5") (pin "9") (pinfunction "9_9") (pintype "passive"))
      (node (ref "J8") (pin "10") (pinfunction "10_10") (pintype "passive"))
      (node (ref "J8") (pin "9") (pinfunction "9_9") (pintype "passive"))
      (node (ref "PS1") (pin "2") (pinfunction "GND_2") (pintype "passive"))
      (node (ref "Q1") (pin "2") (pinfunction "S_2") (pintype "passive"))
      (node (ref "Q2") (pin "2") (pinfunction "S_2") (pintype "passive"))
      (node (ref "R27") (pin "1") (pinfunction "1_1") (pintype "passive"))
      (node (ref "SW1") (pin "2") (pinfunction "2_2") (pintype "passive"))
      (node (ref "SW2") (pin "2") (pinfunction "2_2") (pintype "passive"))
      (node (ref "TP1") (pin "1") (pinfunction "1_1") (pintype "passive"))
      (node (ref "U4") (pin "B1") (pinfunction "GND_B1") (pintype "passive"))
      (node (ref "U6") (pin "B2") (pinfunction "GND_B2") (pintype "passive"))
    )
    (net (code "45") (name "GPIO1V8_A3") (class "Default")
      (node (ref "J14") (pin "2") (pinfunction "2_2") (pintype "passive"))
      (node (ref "J3") (pin "16") (pinfunction "16_16") (pintype "passive"))
      (node (ref "Q2") (pin "1") (pinfunction "G_1") (pintype "passive"))
    )
    (net (code "46") (name "GPIO1V8_H8") (class "Default")
      (node (ref "J13") (pin "2") (pinfunction "2_2") (pintype "passive"))
      (node (ref "J3") (pin "42") (pinfunction "42_42") (pintype "passive"))
    )
    (net (code "47") (name "GPIO_A1_INITN") (class "Default")
      (node (ref "J10") (pin "1") (pinfunction "1_1") (pintype "passive"))
      (node (ref "J3") (pin "15") (pinfunction "15_15") (pintype "passive"))
      (node (ref "SW2") (pin "1") (pinfunction "1_1") (pintype "passive"))
    )
    (net (code "48") (name "GPIO_B1") (class "Default")
      (node (ref "J15") (pin "5") (pinfunction "5_5") (pintype "passive"))
      (node (ref "J3") (pin "17") (pinfunction "17_17") (pintype "passive"))
      (node (ref "SW1") (pin "1") (pinfunction "1_1") (pintype "passive"))
    )
    (net (code "49") (name "GPIO_F1") (class "Default")
      (node (ref "J15") (pin "7") (pinfunction "7_7") (pintype "passive"))
      (node (ref "J3") (pin "19") (pinfunction "19_19") (pintype "passive"))
    )
    (net (code "50") (name "GPIO_G1") (class "Default")
      (node (ref "J3") (pin "21") (pinfunction "21_21") (pintype "passive"))
      (node (ref "J8") (pin "2") (pinfunction "2_2") (pintype "passive"))
    )
    (net (code "51") (name "JTAG_EN") (class "Default")
      (node (ref "J3") (pin "5") (pinfunction "5_5") (pintype "passive"))
      (node (ref "J5") (pin "10") (pinfunction "10_10") (pintype "passive"))
      (node (ref "R28") (pin "1") (pinfunction "1_1") (pintype "passive"))
    )
    (net (code "52") (name "Net-(D1-A)") (class "Default")
      (node (ref "D1") (pin "1") (pinfunction "A_1") (pintype "passive"))
      (node (ref "R1") (pin "2") (pinfunction "2_2") (pintype "passive"))
    )
    (net (code "53") (name "Net-(D3-A)") (class "Default")
      (node (ref "D3") (pin "1") (pinfunction "A_1") (pintype "passive"))
      (node (ref "R3") (pin "2") (pinfunction "2_2") (pintype "passive"))
    )
    (net (code "54") (name "Net-(D5-A)") (class "Default")
      (node (ref "D5") (pin "1") (pinfunction "A_1") (pintype "passive"))
      (node (ref "R18") (pin "2") (pinfunction "2_2") (pintype "passive"))
    )
    (net (code "55") (name "Net-(D5-K)") (class "Default")
      (node (ref "D5") (pin "2") (pinfunction "K_2") (pintype "passive"))
      (node (ref "Q1") (pin "3") (pinfunction "D_3") (pintype "passive"))
    )
    (net (code "56") (name "Net-(D6-A)") (class "Default")
      (node (ref "D6") (pin "1") (pinfunction "A_1") (pintype "passive"))
      (node (ref "R2") (pin "2") (pinfunction "2_2") (pintype "passive"))
    )
    (net (code "57") (name "Net-(D6-K)") (class "Default")
      (node (ref "D6") (pin "2") (pinfunction "K_2") (pintype "passive"))
      (node (ref "Q2") (pin "3") (pinfunction "D_3") (pintype "passive"))
    )
    (net (code "58") (name "Net-(J3-Pad52)") (class "Default")
      (node (ref "J3") (pin "52") (pinfunction "52_52") (pintype "passive"))
      (node (ref "J3") (pin "54") (pinfunction "54_54") (pintype "passive"))
      (node (ref "R5") (pin "2") (pinfunction "2_2") (pintype "passive"))
      (node (ref "T7") (pin "1") (pintype "passive"))
    )
    (net (code "59") (name "Net-(J3-Pad53)") (class "Default")
      (node (ref "J3") (pin "53") (pinfunction "53_53") (pintype "passive"))
      (node (ref "R4") (pin "1") (pinfunction "1_1") (pintype "passive"))
      (node (ref "T6") (pin "1") (pintype "passive"))
    )
    (net (code "60") (name "Net-(J3-Pad55)") (class "Default")
      (node (ref "J3") (pin "55") (pinfunction "55_55") (pintype "passive"))
      (node (ref "R6") (pin "1") (pinfunction "1_1") (pintype "passive"))
      (node (ref "T10") (pin "1") (pintype "passive"))
    )
    (net (code "61") (name "Net-(J3-Pad56)") (class "Default")
      (node (ref "J3") (pin "56") (pinfunction "56_56") (pintype "passive"))
      (node (ref "R7") (pin "2") (pinfunction "2_2") (pintype "passive"))
      (node (ref "T11") (pin "1") (pintype "passive"))
    )
    (net (code "62") (name "Net-(J3-Pad57)") (class "Default")
      (node (ref "J3") (pin "57") (pinfunction "57_57") (pintype "passive"))
      (node (ref "R8") (pin "1") (pinfunction "1_1") (pintype "passive"))
      (node (ref "T14") (pin "1") (pintype "passive"))
    )
    (net (code "63") (name "Net-(J3-Pad58)") (class "Default")
      (node (ref "J3") (pin "58") (pinfunction "58_58") (pintype "passive"))
      (node (ref "R9") (pin "2") (pinfunction "2_2") (pintype "passive"))
      (node (ref "T15") (pin "1") (pintype "passive"))
    )
    (net (code "64") (name "Net-(J3-Pad59)") (class "Default")
      (node (ref "J3") (pin "59") (pinfunction "59_59") (pintype "passive"))
      (node (ref "R10") (pin "1") (pinfunction "1_1") (pintype "passive"))
      (node (ref "T18") (pin "1") (pintype "passive"))
    )
    (net (code "65") (name "Net-(J3-Pad60)") (class "Default")
      (node (ref "J3") (pin "60") (pinfunction "60_60") (pintype "passive"))
      (node (ref "PVDD_4") (pin "1") (pintype "passive"))
    )
    (net (code "66") (name "Net-(J10-Pad3)") (class "Default")
      (node (ref "J10") (pin "3") (pinfunction "3_3") (pintype "passive"))
      (node (ref "R28") (pin "2") (pinfunction "2_2") (pintype "passive"))
    )
    (net (code "67") (name "Net-(PS1-FB)") (class "Default")
      (node (ref "PS1") (pin "1") (pinfunction "FB_1") (pintype "passive"))
      (node (ref "R26") (pin "1") (pinfunction "1_1") (pintype "passive"))
      (node (ref "R27") (pin "2") (pinfunction "2_2") (pintype "passive"))
    )
    (net (code "68") (name "Net-(PS1-OUT)") (class "Default")
      (node (ref "PS1") (pin "6") (pinfunction "OUT_6") (pintype "passive"))
      (node (ref "R15") (pin "2") (pinfunction "2_2") (pintype "passive"))
    )
    (net (code "69") (name "Net-(PS1-SW)") (class "Default")
      (node (ref "L1") (pin "1") (pinfunction "1_1") (pintype "passive"))
      (node (ref "PS1") (pin "4") (pinfunction "SW_4") (pintype "passive"))
    )
    (net (code "70") (name "Net-(PS1-VIN)") (class "Default")
      (node (ref "C2") (pin "2") (pinfunction "2_2") (pintype "passive"))
      (node (ref "PS1") (pin "3") (pinfunction "VIN_3") (pintype "passive"))
      (node (ref "R23") (pin "1") (pinfunction "1_1") (pintype "passive"))
    )
    (net (code "71") (name "Net-(U6-EN)") (class "Default")
      (node (ref "R17") (pin "2") (pinfunction "2_2") (pintype "passive"))
      (node (ref "U6") (pin "B1") (pinfunction "EN_B1") (pintype "passive"))
    )
    (net (code "72") (name "P1V2D") (class "Default")
      (node (ref "C6") (pin "2") (pinfunction "2_2") (pintype "passive"))
      (node (ref "J13") (pin "1") (pinfunction "1_1") (pintype "passive"))
      (node (ref "J7") (pin "1") (pinfunction "1_1") (pintype "passive"))
      (node (ref "U6") (pin "A2") (pinfunction "OUT_A2") (pintype "passive"))
    )
    (net (code "73") (name "P1V8D") (class "Default")
      (node (ref "J13") (pin "5") (pinfunction "5_5") (pintype "passive"))
      (node (ref "J14") (pin "11") (pinfunction "11_11") (pintype "passive"))
      (node (ref "J14") (pin "12") (pinfunction "12_12") (pintype "passive"))
      (node (ref "J7") (pin "5") (pinfunction "5_5") (pintype "passive"))
      (node (ref "J7") (pin "6") (pinfunction "6_6") (pintype "passive"))
      (node (ref "R6") (pin "2") (pinfunction "2_2") (pintype "passive"))
      (node (ref "T9") (pin "1") (pintype "passive"))
    )
    (net (code "74") (name "P1V8_AON") (class "Default")
      (node (ref "J15") (pin "12") (pinfunction "12_12") (pintype "passive"))
      (node (ref "R4") (pin "2") (pinfunction "2_2") (pintype "passive"))
      (node (ref "T5") (pin "1") (pintype "passive"))
    )
    (net (code "75") (name "P3V3D") (class "Default")
      (node (ref "C3") (pin "2") (pinfunction "2_2") (pintype "passive"))
      (node (ref "C5") (pin "2") (pinfunction "2_2") (pintype "passive"))
      (node (ref "J8") (pin "11") (pinfunction "11_11") (pintype "passive"))
      (node (ref "L1") (pin "2") (pinfunction "2_2") (pintype "passive"))
      (node (ref "R15") (pin "1") (pinfunction "1_1") (pintype "passive"))
      (node (ref "R17") (pin "1") (pinfunction "1_1") (pintype "passive"))
      (node (ref "R18") (pin "1") (pinfunction "1_1") (pintype "passive"))
      (node (ref "R2") (pin "1") (pinfunction "1_1") (pintype "passive"))
      (node (ref "R26") (pin "2") (pinfunction "2_2") (pintype "passive"))
      (node (ref "T19") (pin "1") (pintype "passive"))
      (node (ref "U6") (pin "A1") (pinfunction "IN_A1") (pintype "passive"))
    )
    (net (code "76") (name "P3V3_SOM") (class "Default")
      (node (ref "J7") (pin "2") (pinfunction "2_2") (pintype "passive"))
      (node (ref "R3") (pin "1") (pinfunction "1_1") (pintype "passive"))
      (node (ref "R7") (pin "1") (pinfunction "1_1") (pintype "passive"))
      (node (ref "T12") (pin "1") (pintype "passive"))
    )
    (net (code "77") (name "P5V") (class "Default")
      (node (ref "J11") (pin "3") (pinfunction "3_3") (pintype "passive"))
      (node (ref "R1") (pin "1") (pinfunction "1_1") (pintype "passive"))
      (node (ref "R23") (pin "2") (pinfunction "2_2") (pintype "passive"))
      (node (ref "R5") (pin "1") (pinfunction "1_1") (pintype "passive"))
      (node (ref "T8") (pin "1") (pintype "passive"))
      (node (ref "U4") (pin "A2") (pinfunction "VIN_A2") (pintype "passive"))
    )
    (net (code "78") (name "PROGN") (class "Default")
      (node (ref "J14") (pin "4") (pinfunction "4_4") (pintype "passive"))
      (node (ref "J3") (pin "18") (pinfunction "18_18") (pintype "passive"))
    )
    (net (code "79") (name "PVDD_1") (class "Default")
      (node (ref "C4") (pin "2") (pinfunction "2_2") (pintype "passive"))
      (node (ref "J10") (pin "4") (pinfunction "4_4") (pintype "passive"))
      (node (ref "J15") (pin "11") (pinfunction "11_11") (pintype "passive"))
      (node (ref "J5") (pin "1") (pinfunction "1_1") (pintype "passive"))
      (node (ref "J7") (pin "4") (pinfunction "4_4") (pintype "passive"))
      (node (ref "J8") (pin "12") (pinfunction "12_12") (pintype "passive"))
      (node (ref "R8") (pin "2") (pinfunction "2_2") (pintype "passive"))
      (node (ref "T13") (pin "1") (pintype "passive"))
    )
    (net (code "80") (name "PVDD_2") (class "Default")
      (node (ref "J7") (pin "3") (pinfunction "3_3") (pintype "passive"))
      (node (ref "R9") (pin "1") (pinfunction "1_1") (pintype "passive"))
      (node (ref "T16") (pin "1") (pintype "passive"))
    )
    (net (code "81") (name "PVDD_3") (class "Default")
      (node (ref "J13") (pin "3") (pinfunction "3_3") (pintype "passive"))
      (node (ref "R10") (pin "2") (pinfunction "2_2") (pintype "passive"))
      (node (ref "T17") (pin "1") (pintype "passive"))
    )
    (net (code "82") (name "PVUSBC") (class "Default")
      (node (ref "J3") (pin "46") (pinfunction "46_46") (pintype "passive"))
    )
    (net (code "83") (name "SCL") (class "Default")
      (node (ref "J3") (pin "23") (pinfunction "23_23") (pintype "passive"))
      (node (ref "J8") (pin "6") (pinfunction "6_6") (pintype "passive"))
    )
    (net (code "84") (name "SCL33") (class "Default")
      (node (ref "J8") (pin "5") (pinfunction "5_5") (pintype "passive"))
    )
    (net (code "85") (name "SDA") (class "Default")
      (node (ref "J3") (pin "25") (pinfunction "25_25") (pintype "passive"))
      (node (ref "J8") (pin "8") (pinfunction "8_8") (pintype "passive"))
    )
    (net (code "86") (name "SDA33") (class "Default")
      (node (ref "J8") (pin "7") (pinfunction "7_7") (pintype "passive"))
    )
    (net (code "87") (name "SS_RX_N") (class "Default")
      (node (ref "J2") (pin "5") (pinfunction "5_5") (pintype "passive"))
    )
    (net (code "88") (name "SS_RX_P") (class "Default")
      (node (ref "J2") (pin "3") (pinfunction "3_3") (pintype "passive"))
    )
    (net (code "89") (name "SS_TX_N") (class "Default")
      (node (ref "J2") (pin "11") (pinfunction "11_11") (pintype "passive"))
    )
    (net (code "90") (name "SS_TX_P") (class "Default")
      (node (ref "J2") (pin "9") (pinfunction "9_9") (pintype "passive"))
    )
    (net (code "91") (name "TCK") (class "Default")
      (node (ref "J3") (pin "3") (pinfunction "3_3") (pintype "passive"))
      (node (ref "J5") (pin "4") (pinfunction "4_4") (pintype "passive"))
    )
    (net (code "92") (name "TDI") (class "Default")
      (node (ref "J3") (pin "9") (pinfunction "9_9") (pintype "passive"))
      (node (ref "J5") (pin "8") (pinfunction "8_8") (pintype "passive"))
    )
    (net (code "93") (name "TDO") (class "Default")
      (node (ref "J3") (pin "7") (pinfunction "7_7") (pintype "passive"))
      (node (ref "J5") (pin "6") (pinfunction "6_6") (pintype "passive"))
    )
    (net (code "94") (name "TMS") (class "Default")
      (node (ref "J3") (pin "11") (pinfunction "11_11") (pintype "passive"))
      (node (ref "J5") (pin "2") (pinfunction "2_2") (pintype "passive"))
    )
    (net (code "95") (name "USB2_N") (class "Default")
      (node (ref "J2") (pin "17") (pinfunction "17_17") (pintype "passive"))
    )
    (net (code "96") (name "USB2_P") (class "Default")
      (node (ref "J2") (pin "15") (pinfunction "15_15") (pintype "passive"))
    )
    (net (code "97") (name "unconnected-(FID1-FID-Pad1)") (class "Default")
      (node (ref "FID1") (pin "1") (pinfunction "FID_1") (pintype "passive"))
    )
    (net (code "98") (name "unconnected-(FID2-FID-Pad1)") (class "Default")
      (node (ref "FID2") (pin "1") (pinfunction "FID_1") (pintype "passive"))
    )
    (net (code "99") (name "unconnected-(FID3-FID-Pad1)") (class "Default")
      (node (ref "FID3") (pin "1") (pinfunction "FID_1") (pintype "passive"))
    )
    (net (code "100") (name "unconnected-(J2-Pad4)") (class "Default")
      (node (ref "J2") (pin "4") (pinfunction "4_4") (pintype "passive"))
    )
    (net (code "101") (name "unconnected-(J2-Pad6)") (class "Default")
      (node (ref "J2") (pin "6") (pinfunction "6_6") (pintype "passive"))
    )
    (net (code "102") (name "unconnected-(J2-Pad10)") (class "Default")
      (node (ref "J2") (pin "10") (pinfunction "10_10") (pintype "passive"))
    )
    (net (code "103") (name "unconnected-(J2-Pad12)") (class "Default")
      (node (ref "J2") (pin "12") (pinfunction "12_12") (pintype "passive"))
    )
    (net (code "104") (name "unconnected-(J3-Pad20)") (class "Default")
      (node (ref "J3") (pin "20") (pinfunction "20_20") (pintype "passive"))
    )
    (net (code "105") (name "unconnected-(J3-Pad22)") (class "Default")
      (node (ref "J3") (pin "22") (pinfunction "22_22") (pintype "passive"))
    )
    (net (code "106") (name "unconnected-(J3-Pad24)") (class "Default")
      (node (ref "J3") (pin "24") (pinfunction "24_24") (pintype "passive"))
    )
    (net (code "107") (name "unconnected-(J3-Pad26)") (class "Default")
      (node (ref "J3") (pin "26") (pinfunction "26_26") (pintype "passive"))
    )
    (net (code "108") (name "unconnected-(J3-Pad28)") (class "Default")
      (node (ref "J3") (pin "28") (pinfunction "28_28") (pintype "passive"))
    )
    (net (code "109") (name "unconnected-(J3-Pad29)") (class "Default")
      (node (ref "J3") (pin "29") (pinfunction "29_29") (pintype "passive"))
    )
    (net (code "110") (name "unconnected-(J3-Pad30)") (class "Default")
      (node (ref "J3") (pin "30") (pinfunction "30_30") (pintype "passive"))
    )
    (net (code "111") (name "unconnected-(J3-Pad31)") (class "Default")
      (node (ref "J3") (pin "31") (pinfunction "31_31") (pintype "passive"))
    )
    (net (code "112") (name "unconnected-(J3-Pad32)") (class "Default")
      (node (ref "J3") (pin "32") (pinfunction "32_32") (pintype "passive"))
    )
    (net (code "113") (name "unconnected-(J3-Pad33)") (class "Default")
      (node (ref "J3") (pin "33") (pinfunction "33_33") (pintype "passive"))
    )
    (net (code "114") (name "unconnected-(J3-Pad34)") (class "Default")
      (node (ref "J3") (pin "34") (pinfunction "34_34") (pintype "passive"))
    )
    (net (code "115") (name "unconnected-(J3-Pad35)") (class "Default")
      (node (ref "J3") (pin "35") (pinfunction "35_35") (pintype "passive"))
    )
    (net (code "116") (name "unconnected-(J3-Pad36)") (class "Default")
      (node (ref "J3") (pin "36") (pinfunction "36_36") (pintype "passive"))
    )
    (net (code "117") (name "unconnected-(J3-Pad37)") (class "Default")
      (node (ref "J3") (pin "37") (pinfunction "37_37") (pintype "passive"))
    )
    (net (code "118") (name "unconnected-(J3-Pad38)") (class "Default")
      (node (ref "J3") (pin "38") (pinfunction "38_38") (pintype "passive"))
    )
    (net (code "119") (name "unconnected-(J3-Pad39)") (class "Default")
      (node (ref "J3") (pin "39") (pinfunction "39_39") (pintype "passive"))
    )
    (net (code "120") (name "unconnected-(J3-Pad41)") (class "Default")
      (node (ref "J3") (pin "41") (pinfunction "41_41") (pintype "passive"))
    )
    (net (code "121") (name "unconnected-(J3-Pad43)") (class "Default")
      (node (ref "J3") (pin "43") (pinfunction "43_43") (pintype "passive"))
    )
    (net (code "122") (name "unconnected-(J3-Pad45)") (class "Default")
      (node (ref "J3") (pin "45") (pinfunction "45_45") (pintype "passive"))
    )
    (net (code "123") (name "unconnected-(J5-Pad7)") (class "Default")
      (node (ref "J5") (pin "7") (pinfunction "7_7") (pintype "passive+no_connect"))
    )
    (net (code "124") (name "unconnected-(J8-Pad1)") (class "Default")
      (node (ref "J8") (pin "1") (pinfunction "1_1") (pintype "passive"))
    )
    (net (code "125") (name "unconnected-(J8-Pad3)") (class "Default")
      (node (ref "J8") (pin "3") (pinfunction "3_3") (pintype "passive"))
    )
    (net (code "126") (name "unconnected-(J8-Pad4)") (class "Default")
      (node (ref "J8") (pin "4") (pinfunction "4_4") (pintype "passive"))
    )
    (net (code "127") (name "unconnected-(J13-Pad6)") (class "Default")
      (node (ref "J13") (pin "6") (pinfunction "6_6") (pintype "passive"))
    )
    (net (code "128") (name "unconnected-(J15-Pad2)") (class "Default")
      (node (ref "J15") (pin "2") (pinfunction "2_2") (pintype "passive"))
    )
    (net (code "129") (name "unconnected-(J15-Pad3)") (class "Default")
      (node (ref "J15") (pin "3") (pinfunction "3_3") (pintype "passive"))
    )
    (net (code "130") (name "unconnected-(J15-Pad4)") (class "Default")
      (node (ref "J15") (pin "4") (pinfunction "4_4") (pintype "passive"))
    )
    (net (code "131") (name "unconnected-(SW1-GND-PadS1)") (class "Default")
      (node (ref "SW1") (pin "S1") (pinfunction "GND_S1") (pintype "passive"))
    )
    (net (code "132") (name "unconnected-(SW2-GND-PadS1)") (class "Default")
      (node (ref "SW2") (pin "S1") (pinfunction "GND_S1") (pintype "passive"))
    )
  )
)
